# bnc_BOB.net
KiCad netlist of a schematic drawn in EAGLE
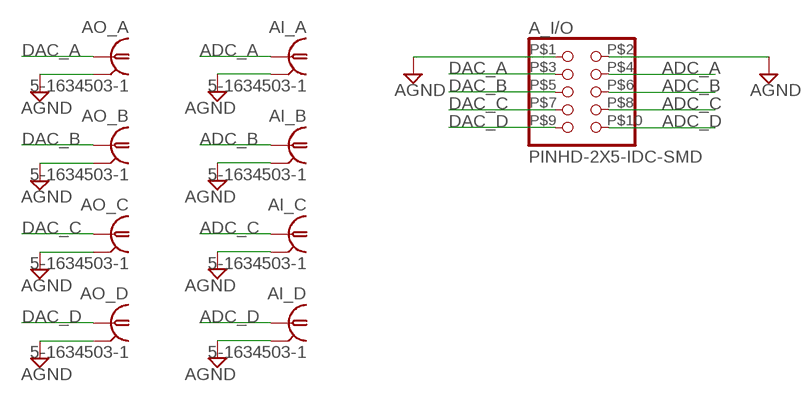
[diagram p0: schematic, sheet 1]

(export (version "E")
  (design (tool "Eeschema 10.0.6"))
  (components
    (comp (ref "AI_A")
      (value "5-1634503-1")
      (footprint "eagle-import:B35N61")
      (fields (field (name "MF") "TE Connectivity"))
      (libsource (lib "eagle-import") (part "BN35N61"))
    )
    (comp (ref "AI_B")
      (value "5-1634503-1")
      (footprint "eagle-import:B35N61")
      (fields (field (name "MF") "TE Connectivity"))
      (libsource (lib "eagle-import") (part "BN35N61"))
    )
    (comp (ref "AI_C")
      (value "5-1634503-1")
      (footprint "eagle-import:B35N61")
      (fields (field (name "MF") "TE Connectivity"))
      (libsource (lib "eagle-import") (part "BN35N61"))
    )
    (comp (ref "AI_D")
      (value "5-1634503-1")
      (footprint "eagle-import:B35N61")
      (fields (field (name "MF") "TE Connectivity"))
      (libsource (lib "eagle-import") (part "BN35N61"))
    )
    (comp (ref "AO_A")
      (value "5-1634503-1")
      (footprint "eagle-import:B35N61")
      (fields (field (name "MF") "TE Connectivity"))
      (libsource (lib "eagle-import") (part "BN35N61"))
    )
    (comp (ref "AO_B")
      (value "5-1634503-1")
      (footprint "eagle-import:B35N61")
      (fields (field (name "MF") "TE Connectivity"))
      (libsource (lib "eagle-import") (part "BN35N61"))
    )
    (comp (ref "AO_C")
      (value "5-1634503-1")
      (footprint "eagle-import:B35N61")
      (fields (field (name "MF") "TE Connectivity"))
      (libsource (lib "eagle-import") (part "BN35N61"))
    )
    (comp (ref "AO_D")
      (value "5-1634503-1")
      (footprint "eagle-import:B35N61")
      (fields (field (name "MF") "TE Connectivity"))
      (libsource (lib "eagle-import") (part "BN35N61"))
    )
    (comp (ref "A_I/O")
      (value "PINHD-2X5-IDC-SMD")
      (footprint "eagle-import:2X05-IDC-SMD")
      (fields (field (name "MPN") "SBH11-NBPC-D05-SM-BK"))
      (libsource (lib "eagle-import") (part "PINHD-2X5-IDC-SMD"))
    )
  )
  (nets
    (net (code "1") (name "/ADC_A") (class "Default")
      (node (ref "AI_A") (pin "1") (pinfunction "1_1") (pintype "passive"))
      (node (ref "A_I/O") (pin "P$4") (pinfunction "4_P$4") (pintype "passive"))
    )
    (net (code "2") (name "/ADC_B") (class "Default")
      (node (ref "AI_B") (pin "1") (pinfunction "1_1") (pintype "passive"))
      (node (ref "A_I/O") (pin "P$6") (pinfunction "6_P$6") (pintype "passive"))
    )
    (net (code "3") (name "/ADC_C") (class "Default")
      (node (ref "AI_C") (pin "1") (pinfunction "1_1") (pintype "passive"))
      (node (ref "A_I/O") (pin "P$8") (pinfunction "8_P$8") (pintype "passive"))
    )
    (net (code "4") (name "/ADC_D") (class "Default")
      (node (ref "AI_D") (pin "1") (pinfunction "1_1") (pintype "passive"))
      (node (ref "A_I/O") (pin "P$10") (pinfunction "10_P$10") (pintype "passive"))
    )
    (net (code "5") (name "/DAC_A") (class "Default")
      (node (ref "AO_A") (pin "1") (pinfunction "1_1") (pintype "passive"))
      (node (ref "A_I/O") (pin "P$3") (pinfunction "3_P$3") (pintype "passive"))
    )
    (net (code "6") (name "/DAC_B") (class "Default")
      (node (ref "AO_B") (pin "1") (pinfunction "1_1") (pintype "passive"))
      (node (ref "A_I/O") (pin "P$5") (pinfunction "5_P$5") (pintype "passive"))
    )
    (net (code "7") (name "/DAC_C") (class "Default")
      (node (ref "AO_C") (pin "1") (pinfunction "1_1") (pintype "passive"))
      (node (ref "A_I/O") (pin "P$7") (pinfunction "7_P$7") (pintype "passive"))
    )
    (net (code "8") (name "/DAC_D") (class "Default")
      (node (ref "AO_D") (pin "1") (pinfunction "1_1") (pintype "passive"))
      (node (ref "A_I/O") (pin "P$9") (pinfunction "9_P$9") (pintype "passive"))
    )
    (net (code "9") (name "AGND") (class "Default")
      (node (ref "AI_A") (pin "2") (pinfunction "2_2") (pintype "passive"))
      (node (ref "AI_A") (pin "3") (pinfunction "2_3") (pintype "passive"))
      (node (ref "AI_A") (pin "4") (pinfunction "2_4") (pintype "passive"))
      (node (ref "AI_A") (pin "5") (pinfunction "2_5") (pintype "passive"))
      (node (ref "AI_B") (pin "2") (pinfunction "2_2") (pintype "passive"))
      (node (ref "AI_B") (pin "3") (pinfunction "2_3") (pintype "passive"))
      (node (ref "AI_B") (pin "4") (pinfunction "2_4") (pintype "passive"))
      (node (ref "AI_B") (pin "5") (pinfunction "2_5") (pintype "passive"))
      (node (ref "AI_C") (pin "2") (pinfunction "2_2") (pintype "passive"))
      (node (ref "AI_C") (pin "3") (pinfunction "2_3") (pintype "passive"))
      (node (ref "AI_C") (pin "4") (pinfunction "2_4") (pintype "passive"))
      (node (ref "AI_C") (pin "5") (pinfunction "2_5") (pintype "passive"))
      (node (ref "AI_D") (pin "2") (pinfunction "2_2") (pintype "passive"))
      (node (ref "AI_D") (pin "3") (pinfunction "2_3") (pintype "passive"))
      (node (ref "AI_D") (pin "4") (pinfunction "2_4") (pintype "passive"))
      (node (ref "AI_D") (pin "5") (pinfunction "2_5") (pintype "passive"))
      (node (ref "AO_A") (pin "2") (pinfunction "2_2") (pintype "passive"))
      (node (ref "AO_A") (pin "3") (pinfunction "2_3") (pintype "passive"))
      (node (ref "AO_A") (pin "4") (pinfunction "2_4") (pintype "passive"))
      (node (ref "AO_A") (pin "5") (pinfunction "2_5") (pintype "passive"))
      (node (ref "AO_B") (pin "2") (pinfunction "2_2") (pintype "passive"))
      (node (ref "AO_B") (pin "3") (pinfunction "2_3") (pintype "passive"))
      (node (ref "AO_B") (pin "4") (pinfunction "2_4") (pintype "passive"))
      (node (ref "AO_B") (pin "5") (pinfunction "2_5") (pintype "passive"))
      (node (ref "AO_C") (pin "2") (pinfunction "2_2") (pintype "passive"))
      (node (ref "AO_C") (pin "3") (pinfunction "2_3") (pintype "passive"))
      (node (ref "AO_C") (pin "4") (pinfunction "2_4") (pintype "passive"))
      (node (ref "AO_C") (pin "5") (pinfunction "2_5") (pintype "passive"))
      (node (ref "AO_D") (pin "2") (pinfunction "2_2") (pintype "passive"))
      (node (ref "AO_D") (pin "3") (pinfunction "2_3") (pintype "passive"))
      (node (ref "AO_D") (pin "4") (pinfunction "2_4") (pintype "passive"))
      (node (ref "AO_D") (pin "5") (pinfunction "2_5") (pintype "passive"))
      (node (ref "A_I/O") (pin "P$1") (pinfunction "1_P$1") (pintype "passive"))
      (node (ref "A_I/O") (pin "P$2") (pinfunction "2_P$2") (pintype "passive"))
    )
  )
)
